# MC-10_Mod_A_V.net
KiCad netlist of a schematic drawn in EAGLE
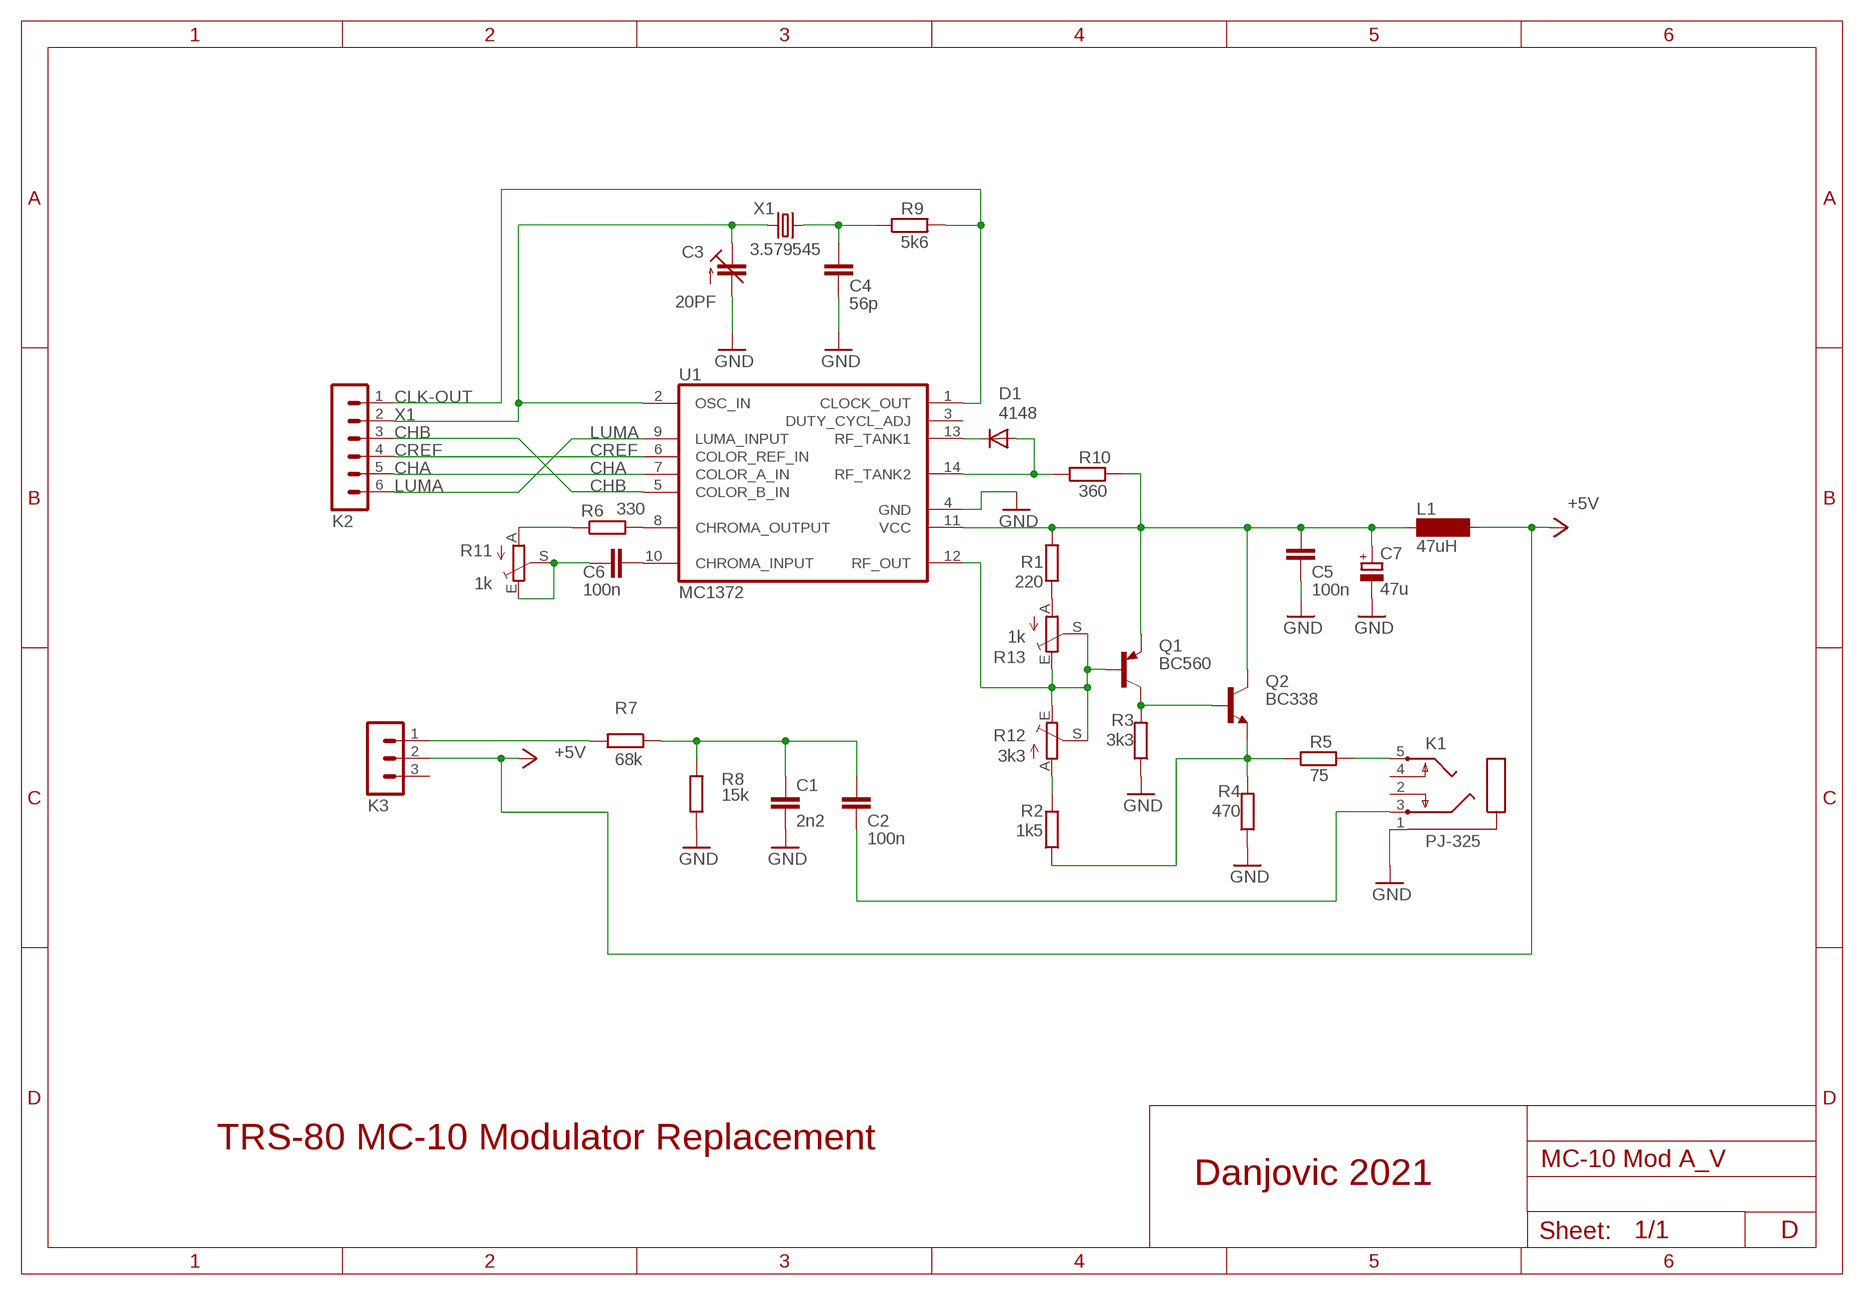
[diagram p0: schematic, sheet 1]

(export (version "E")
  (design (tool "Eeschema 10.0.6"))
  (components
    (comp (ref "C1")
      (value "2n2")
      (footprint "eagle-import:C050-024X044")
      (libsource (lib "eagle-import") (part "C-EU050-024X044"))
    )
    (comp (ref "C2")
      (value "100n")
      (footprint "eagle-import:C050-024X044")
      (libsource (lib "eagle-import") (part "C-EU050-024X044"))
    )
    (comp (ref "C3")
      (value "20PF")
      (footprint "eagle-import:CTRIM3050.504")
      (libsource (lib "eagle-import") (part "C-TRIMM3050.504"))
    )
    (comp (ref "C4")
      (value "56p")
      (footprint "eagle-import:C025-024X044")
      (libsource (lib "eagle-import") (part "C-EU025-024X044"))
    )
    (comp (ref "C5")
      (value "100n")
      (footprint "eagle-import:C050-024X044")
      (libsource (lib "eagle-import") (part "C-EU050-024X044"))
    )
    (comp (ref "C6")
      (value "100n")
      (footprint "eagle-import:C050-024X044")
      (libsource (lib "eagle-import") (part "C-EU050-024X044"))
    )
    (comp (ref "C7")
      (value "47u")
      (footprint "eagle-import:E2,5-5")
      (libsource (lib "eagle-import") (part "CPOL-EUE2.5-5"))
    )
    (comp (ref "D1")
      (value "4148")
      (footprint "eagle-import:D-5")
      (libsource (lib "eagle-import") (part "DIODE-D-5"))
    )
    (comp (ref "K1")
      (value "PJ-325")
      (footprint "eagle-import:PJ325")
      (libsource (lib "eagle-import") (part "PJ-325"))
    )
    (comp (ref "K2")
      (value "MA06-1")
      (footprint "eagle-import:MA06-1")
      (libsource (lib "eagle-import") (part "MA06-1"))
    )
    (comp (ref "K3")
      (value "MA03-1")
      (footprint "eagle-import:MA03-1")
      (libsource (lib "eagle-import") (part "MA03-1"))
    )
    (comp (ref "L1")
      (value "47uH")
      (footprint "eagle-import:BS75")
      (libsource (lib "eagle-import") (part "BS75"))
    )
    (comp (ref "Q1")
      (value "BC560")
      (footprint "eagle-import:TO92-EBC")
      (libsource (lib "eagle-import") (part "BC327"))
    )
    (comp (ref "Q2")
      (value "BC338")
      (footprint "eagle-import:TO92-EBC")
      (libsource (lib "eagle-import") (part "BC338"))
    )
    (comp (ref "R1")
      (value "220")
      (footprint "eagle-import:0204_7")
      (libsource (lib "eagle-import") (part "R-EU_0204/7"))
    )
    (comp (ref "R2")
      (value "1k5")
      (footprint "eagle-import:0204_7")
      (libsource (lib "eagle-import") (part "R-EU_0204/7"))
    )
    (comp (ref "R3")
      (value "3k3")
      (footprint "eagle-import:0204_7")
      (libsource (lib "eagle-import") (part "R-EU_0204/7"))
    )
    (comp (ref "R4")
      (value "470")
      (footprint "eagle-import:0204_7")
      (libsource (lib "eagle-import") (part "R-EU_0204/7"))
    )
    (comp (ref "R5")
      (value "75")
      (footprint "eagle-import:0204_7")
      (libsource (lib "eagle-import") (part "R-EU_0204/7"))
    )
    (comp (ref "R6")
      (value "330")
      (footprint "eagle-import:0204_7")
      (libsource (lib "eagle-import") (part "R-EU_0204/7"))
    )
    (comp (ref "R7")
      (value "68k")
      (footprint "eagle-import:0204_7")
      (libsource (lib "eagle-import") (part "R-EU_0204/7"))
    )
    (comp (ref "R8")
      (value "15k")
      (footprint "eagle-import:0204_7")
      (libsource (lib "eagle-import") (part "R-EU_0204/7"))
    )
    (comp (ref "R9")
      (value "5k6")
      (footprint "eagle-import:0204_7")
      (libsource (lib "eagle-import") (part "R-EU_0204/7"))
    )
    (comp (ref "R10")
      (value "360")
      (footprint "eagle-import:0204_7")
      (libsource (lib "eagle-import") (part "R-EU_0204/7"))
    )
    (comp (ref "R11")
      (value "1k")
      (footprint "eagle-import:RS3")
      (libsource (lib "eagle-import") (part "TRIM_EU-RS3"))
    )
    (comp (ref "R12")
      (value "3k3")
      (footprint "eagle-import:RS3")
      (libsource (lib "eagle-import") (part "TRIM_EU-RS3"))
    )
    (comp (ref "R13")
      (value "1k")
      (footprint "eagle-import:RS3")
      (libsource (lib "eagle-import") (part "TRIM_EU-RS3"))
    )
    (comp (ref "U1")
      (value "MC1372")
      (footprint "eagle-import:DIL14")
      (libsource (lib "eagle-import") (part "MC1372"))
    )
    (comp (ref "X1")
      (value "3.579545")
      (footprint "eagle-import:HC49U70")
      (libsource (lib "eagle-import") (part "CRYSTALHC49U70"))
    )
  )
  (nets
    (net (code "1") (name "+5V") (class "Default")
      (node (ref "K3") (pin "2") (pinfunction "2_2") (pintype "passive"))
      (node (ref "L1") (pin "2") (pinfunction "2_2") (pintype "passive"))
    )
    (net (code "2") (name "/CHA") (class "Default")
      (node (ref "K2") (pin "5") (pinfunction "5_5") (pintype "passive"))
      (node (ref "U1") (pin "7") (pinfunction "COLOR_A_IN_7") (pintype "input"))
    )
    (net (code "3") (name "/CHB") (class "Default")
      (node (ref "K2") (pin "3") (pinfunction "3_3") (pintype "passive"))
      (node (ref "U1") (pin "5") (pinfunction "COLOR_B_IN_5") (pintype "input"))
    )
    (net (code "4") (name "/CLK-OUT") (class "Default")
      (node (ref "K2") (pin "1") (pinfunction "1_1") (pintype "passive"))
      (node (ref "R9") (pin "2") (pinfunction "2_2") (pintype "passive"))
      (node (ref "U1") (pin "1") (pinfunction "CLOCK_OUT_1") (pintype "output"))
    )
    (net (code "5") (name "/CREF") (class "Default")
      (node (ref "K2") (pin "4") (pinfunction "4_4") (pintype "passive"))
      (node (ref "U1") (pin "6") (pinfunction "COLOR_REF_IN_6") (pintype "input"))
    )
    (net (code "6") (name "/LUMA") (class "Default")
      (node (ref "K2") (pin "6") (pinfunction "6_6") (pintype "passive"))
      (node (ref "U1") (pin "9") (pinfunction "LUMA_INPUT_9") (pintype "input"))
    )
    (net (code "7") (name "/X1") (class "Default")
      (node (ref "C3") (pin "1") (pinfunction "E_1") (pintype "passive"))
      (node (ref "K2") (pin "2") (pinfunction "2_2") (pintype "passive"))
      (node (ref "U1") (pin "2") (pinfunction "OSC_IN_2") (pintype "tri_state"))
      (node (ref "X1") (pin "1") (pinfunction "1_1") (pintype "passive"))
    )
    (net (code "8") (name "GND") (class "Default")
      (node (ref "C1") (pin "2") (pinfunction "2_2") (pintype "passive"))
      (node (ref "C3") (pin "2") (pinfunction "A_2") (pintype "passive"))
      (node (ref "C4") (pin "2") (pinfunction "2_2") (pintype "passive"))
      (node (ref "C5") (pin "2") (pinfunction "2_2") (pintype "passive"))
      (node (ref "C7") (pin "-") (pinfunction "-_-") (pintype "passive"))
      (node (ref "K1") (pin "1") (pinfunction "1_1") (pintype "passive"))
      (node (ref "R3") (pin "1") (pinfunction "1_1") (pintype "passive"))
      (node (ref "R4") (pin "1") (pinfunction "1_1") (pintype "passive"))
      (node (ref "R8") (pin "1") (pinfunction "1_1") (pintype "passive"))
      (node (ref "U1") (pin "4") (pinfunction "GND_4") (pintype "power_in"))
    )
    (net (code "9") (name "Net-(C1-Pad1)") (class "Default")
      (node (ref "C1") (pin "1") (pinfunction "1_1") (pintype "passive"))
      (node (ref "C2") (pin "1") (pinfunction "1_1") (pintype "passive"))
      (node (ref "R7") (pin "1") (pinfunction "1_1") (pintype "passive"))
      (node (ref "R8") (pin "2") (pinfunction "2_2") (pintype "passive"))
    )
    (net (code "10") (name "Net-(C2-Pad2)") (class "Default")
      (node (ref "C2") (pin "2") (pinfunction "2_2") (pintype "passive"))
      (node (ref "K1") (pin "3") (pinfunction "3_3") (pintype "passive"))
    )
    (net (code "11") (name "Net-(C4-Pad1)") (class "Default")
      (node (ref "C4") (pin "1") (pinfunction "1_1") (pintype "passive"))
      (node (ref "R9") (pin "1") (pinfunction "1_1") (pintype "passive"))
      (node (ref "X1") (pin "2") (pinfunction "2_2") (pintype "passive"))
    )
    (net (code "12") (name "Net-(C6-Pad1)") (class "Default")
      (node (ref "C6") (pin "1") (pinfunction "1_1") (pintype "passive"))
      (node (ref "R11") (pin "E") (pinfunction "E_E") (pintype "passive"))
      (node (ref "R11") (pin "S") (pinfunction "S_S") (pintype "passive"))
    )
    (net (code "13") (name "Net-(K1-Pad5)") (class "Default")
      (node (ref "K1") (pin "5") (pinfunction "5_5") (pintype "passive"))
      (node (ref "R5") (pin "2") (pinfunction "2_2") (pintype "passive"))
    )
    (net (code "14") (name "Net-(K3-Pad1)") (class "Default")
      (node (ref "K3") (pin "1") (pinfunction "1_1") (pintype "passive"))
      (node (ref "R7") (pin "2") (pinfunction "2_2") (pintype "passive"))
    )
    (net (code "15") (name "Net-(Q1-PadC)") (class "Default")
      (node (ref "Q1") (pin "C") (pinfunction "C_C") (pintype "passive"))
      (node (ref "Q2") (pin "B") (pinfunction "B_B") (pintype "passive"))
      (node (ref "R3") (pin "2") (pinfunction "2_2") (pintype "passive"))
    )
    (net (code "16") (name "Net-(Q2-PadE)") (class "Default")
      (node (ref "Q2") (pin "E") (pinfunction "E_E") (pintype "passive"))
      (node (ref "R2") (pin "1") (pinfunction "1_1") (pintype "passive"))
      (node (ref "R4") (pin "2") (pinfunction "2_2") (pintype "passive"))
      (node (ref "R5") (pin "1") (pinfunction "1_1") (pintype "passive"))
    )
    (net (code "17") (name "Net-(R1-Pad1)") (class "Default")
      (node (ref "R1") (pin "1") (pinfunction "1_1") (pintype "passive"))
      (node (ref "R13") (pin "A") (pinfunction "A_A") (pintype "passive"))
    )
    (net (code "18") (name "Net-(R11-PadA)") (class "Default")
      (node (ref "R11") (pin "A") (pinfunction "A_A") (pintype "passive"))
      (node (ref "R6") (pin "1") (pinfunction "1_1") (pintype "passive"))
    )
    (net (code "19") (name "Net-(R12-PadA)") (class "Default")
      (node (ref "R12") (pin "A") (pinfunction "A_A") (pintype "passive"))
      (node (ref "R2") (pin "2") (pinfunction "2_2") (pintype "passive"))
    )
    (net (code "20") (name "Net-(U1-CHROMA_INPUT)") (class "Default")
      (node (ref "C6") (pin "2") (pinfunction "2_2") (pintype "passive"))
      (node (ref "U1") (pin "10") (pinfunction "CHROMA_INPUT_10") (pintype "input"))
    )
    (net (code "21") (name "Net-(U1-CHROMA_OUTPUT)") (class "Default")
      (node (ref "R6") (pin "2") (pinfunction "2_2") (pintype "passive"))
      (node (ref "U1") (pin "8") (pinfunction "CHROMA_OUTPUT_8") (pintype "output"))
    )
    (net (code "22") (name "Net-(U1-RF_OUT)") (class "Default")
      (node (ref "Q1") (pin "B") (pinfunction "B_B") (pintype "passive"))
      (node (ref "R12") (pin "E") (pinfunction "E_E") (pintype "passive"))
      (node (ref "R12") (pin "S") (pinfunction "S_S") (pintype "passive"))
      (node (ref "R13") (pin "E") (pinfunction "E_E") (pintype "passive"))
      (node (ref "R13") (pin "S") (pinfunction "S_S") (pintype "passive"))
      (node (ref "U1") (pin "12") (pinfunction "RF_OUT_12") (pintype "output"))
    )
    (net (code "23") (name "Net-(U1-RF_TANK1)") (class "Default")
      (node (ref "D1") (pin "C") (pinfunction "C_C") (pintype "passive"))
      (node (ref "U1") (pin "13") (pinfunction "RF_TANK1_13") (pintype "tri_state"))
    )
    (net (code "24") (name "Net-(U1-RF_TANK2)") (class "Default")
      (node (ref "D1") (pin "A") (pinfunction "A_A") (pintype "passive"))
      (node (ref "R10") (pin "1") (pinfunction "1_1") (pintype "passive"))
      (node (ref "U1") (pin "14") (pinfunction "RF_TANK2_14") (pintype "tri_state"))
    )
    (net (code "25") (name "Net-(U1-VCC)") (class "Default")
      (node (ref "C5") (pin "1") (pinfunction "1_1") (pintype "passive"))
      (node (ref "C7") (pin "+") (pinfunction "+_+") (pintype "passive"))
      (node (ref "L1") (pin "1") (pinfunction "1_1") (pintype "passive"))
      (node (ref "Q1") (pin "E") (pinfunction "E_E") (pintype "passive"))
      (node (ref "Q2") (pin "C") (pinfunction "C_C") (pintype "passive"))
      (node (ref "R1") (pin "2") (pinfunction "2_2") (pintype "passive"))
      (node (ref "R10") (pin "2") (pinfunction "2_2") (pintype "passive"))
      (node (ref "U1") (pin "11") (pinfunction "VCC_11") (pintype "power_in"))
    )
    (net (code "26") (name "unconnected-(K1-Pad2)") (class "Default")
      (node (ref "K1") (pin "2") (pinfunction "2_2") (pintype "passive"))
    )
    (net (code "27") (name "unconnected-(K1-Pad4)") (class "Default")
      (node (ref "K1") (pin "4") (pinfunction "4_4") (pintype "passive"))
    )
    (net (code "28") (name "unconnected-(K3-Pad3)") (class "Default")
      (node (ref "K3") (pin "3") (pinfunction "3_3") (pintype "passive"))
    )
    (net (code "29") (name "unconnected-(U1-DUTY_CYCL_ADJ-Pad3)") (class "Default")
      (node (ref "U1") (pin "3") (pinfunction "DUTY_CYCL_ADJ_3") (pintype "input"))
    )
  )
)
